# LEDproject_11_18_18.net
KiCad netlist of a schematic drawn in EAGLE
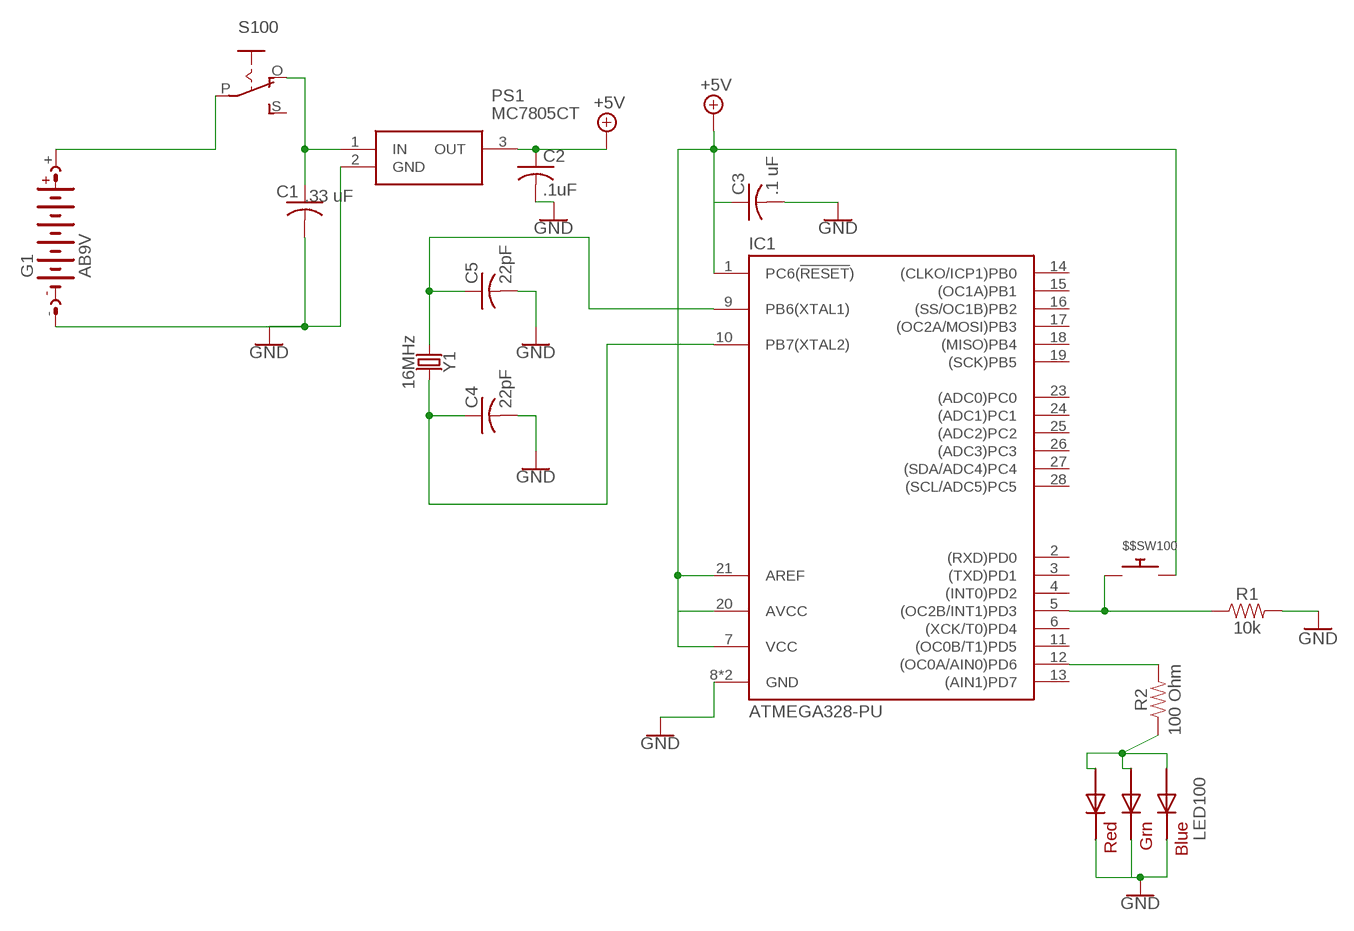
[diagram p0: schematic, sheet 1]

(export (version "E")
  (design (tool "Eeschema 10.0.6"))
  (components
    (comp (ref "$$SW100")
      (value "SWITCH_PUSHBUTTONEVQ-PE")
      (footprint "eagle-import:TACT_PANA-EVQ")
      (libsource (lib "eagle-import") (part "SWITCH_PUSHBUTTONEVQ-PE"))
    )
    (comp (ref "C1")
      (value "C-US025-030X050")
      (footprint "eagle-import:C025-030X050")
      (fields (field (name "BYPASS1") ".33 uF"))
      (libsource (lib "eagle-import") (part "C-US025-030X050"))
    )
    (comp (ref "C2")
      (value ".1uF")
      (footprint "eagle-import:C025-030X050")
      (libsource (lib "eagle-import") (part "C-US025-030X050"))
    )
    (comp (ref "C3")
      (value ".1 uF")
      (footprint "eagle-import:C025-030X050")
      (libsource (lib "eagle-import") (part "C-US025-030X050"))
    )
    (comp (ref "C4")
      (value "22pF")
      (footprint "eagle-import:C025-030X050")
      (libsource (lib "eagle-import") (part "C-US025-030X050"))
    )
    (comp (ref "C5")
      (value "22pF")
      (footprint "eagle-import:C025-030X050")
      (libsource (lib "eagle-import") (part "C-US025-030X050"))
    )
    (comp (ref "G1")
      (value "AB9V")
      (footprint "eagle-import:AB9V")
      (libsource (lib "eagle-import") (part "AB9V"))
    )
    (comp (ref "IC1")
      (value "ATMEGA328-PU")
      (footprint "eagle-import:DIL28")
      (fields (field (name "DIGI-KEY_PART_NUMBER") "ATMEGA328-PU-ND") (field (name "MF") "Microchip"))
      (libsource (lib "eagle-import") (part "ATMEGA328-PU"))
    )
    (comp (ref "LED100")
      (value "RGBLED5050")
      (footprint "eagle-import:RGBLED5050")
      (libsource (lib "eagle-import") (part "RGBLED5050"))
    )
    (comp (ref "PS1")
      (value "MC7805CT")
      (footprint "eagle-import:TO254P482X997X1968-3P")
      (fields (field (name "MOUSER_PART_NUMBER") "863-MC7805CT"))
      (libsource (lib "eagle-import") (part "MC7805CT"))
    )
    (comp (ref "R1")
      (value "10k")
      (footprint "eagle-import:AXIAL-0.3")
      (libsource (lib "eagle-import") (part "10KOHM-HORIZ-1/6W-5%"))
    )
    (comp (ref "R2")
      (value "100 Ohm")
      (footprint "eagle-import:AXIAL-0.3")
      (libsource (lib "eagle-import") (part "10OHM-HORIZ-1/4W-1%"))
    )
    (comp (ref "S100")
      (value "EG1218S")
      (footprint "eagle-import:EG1218")
      (libsource (lib "eagle-import") (part "EG1218S"))
    )
    (comp (ref "Y1")
      (value "16MHz")
      (footprint "eagle-import:HC49US")
      (libsource (lib "eagle-import") (part "CRYSTAL-16MHZPTH-HC49US"))
    )
  )
  (nets
    (net (code "1") (name "+5V") (class "Default")
      (node (ref "$$SW100") (pin "P$2") (pinfunction "P$2_P$2") (pintype "passive"))
      (node (ref "C2") (pin "1") (pinfunction "1_1") (pintype "passive"))
      (node (ref "C3") (pin "1") (pinfunction "1_1") (pintype "passive"))
      (node (ref "IC1") (pin "1") (pinfunction "PC6(~{RESET})_1") (pintype "bidirectional"))
      (node (ref "IC1") (pin "20") (pinfunction "AVCC_20") (pintype "power_in"))
      (node (ref "IC1") (pin "21") (pinfunction "AREF_21") (pintype "passive"))
      (node (ref "IC1") (pin "7") (pinfunction "VCC_7") (pintype "power_in"))
      (node (ref "PS1") (pin "3") (pinfunction "OUT_3") (pintype "output"))
    )
    (net (code "2") (name "GND") (class "Default")
      (node (ref "C1") (pin "2") (pinfunction "2_2") (pintype "passive"))
      (node (ref "C2") (pin "2") (pinfunction "2_2") (pintype "passive"))
      (node (ref "C3") (pin "2") (pinfunction "2_2") (pintype "passive"))
      (node (ref "C4") (pin "2") (pinfunction "2_2") (pintype "passive"))
      (node (ref "C5") (pin "2") (pinfunction "2_2") (pintype "passive"))
      (node (ref "G1") (pin "-") (pinfunction "-_-") (pintype "passive"))
      (node (ref "IC1") (pin "22") (pinfunction "GND_22") (pintype "power_in"))
      (node (ref "IC1") (pin "8") (pinfunction "GND_8") (pintype "power_in"))
      (node (ref "LED100") (pin "4") (pinfunction "BLUE_C_4") (pintype "bidirectional"))
      (node (ref "LED100") (pin "5") (pinfunction "RED_C_5") (pintype "bidirectional"))
      (node (ref "LED100") (pin "6") (pinfunction "GREEN_C_6") (pintype "bidirectional"))
      (node (ref "PS1") (pin "2") (pinfunction "GND_2") (pintype "power_in"))
      (node (ref "R1") (pin "P$2") (pinfunction "2_P$2") (pintype "passive"))
    )
    (net (code "3") (name "Net-(G1-Pad+)") (class "Default")
      (node (ref "G1") (pin "+") (pinfunction "+_+") (pintype "passive"))
      (node (ref "S100") (pin "P") (pinfunction "P_P") (pintype "passive"))
    )
    (net (code "4") (name "Net-(IC1-(OC0A{slash}AIN0)PD6)") (class "Default")
      (node (ref "IC1") (pin "12") (pinfunction "(OC0A/AIN0)PD6_12") (pintype "bidirectional"))
      (node (ref "R2") (pin "P$2") (pinfunction "2_P$2") (pintype "passive"))
    )
    (net (code "5") (name "Net-(IC1-(OC2B{slash}INT1)PD3)") (class "Default")
      (node (ref "$$SW100") (pin "P$1") (pinfunction "P$1_P$1") (pintype "passive"))
      (node (ref "IC1") (pin "5") (pinfunction "(OC2B/INT1)PD3_5") (pintype "bidirectional"))
      (node (ref "R1") (pin "P$1") (pinfunction "1_P$1") (pintype "passive"))
    )
    (net (code "6") (name "Net-(IC1-PB6(XTAL1))") (class "Default")
      (node (ref "C5") (pin "1") (pinfunction "1_1") (pintype "passive"))
      (node (ref "IC1") (pin "9") (pinfunction "PB6(XTAL1)_9") (pintype "bidirectional"))
      (node (ref "Y1") (pin "1") (pinfunction "1_1") (pintype "passive"))
    )
    (net (code "7") (name "Net-(IC1-PB7(XTAL2))") (class "Default")
      (node (ref "C4") (pin "1") (pinfunction "1_1") (pintype "passive"))
      (node (ref "IC1") (pin "10") (pinfunction "PB7(XTAL2)_10") (pintype "bidirectional"))
      (node (ref "Y1") (pin "2") (pinfunction "2_2") (pintype "passive"))
    )
    (net (code "8") (name "Net-(LED100-BLUE_A)") (class "Default")
      (node (ref "LED100") (pin "1") (pinfunction "GREEN_A_1") (pintype "bidirectional"))
      (node (ref "LED100") (pin "2") (pinfunction "RED_A_2") (pintype "bidirectional"))
      (node (ref "LED100") (pin "3") (pinfunction "BLUE_A_3") (pintype "bidirectional"))
      (node (ref "R2") (pin "P$1") (pinfunction "1_P$1") (pintype "passive"))
    )
    (net (code "9") (name "Net-(PS1-IN)") (class "Default")
      (node (ref "C1") (pin "1") (pinfunction "1_1") (pintype "passive"))
      (node (ref "PS1") (pin "1") (pinfunction "IN_1") (pintype "input"))
      (node (ref "S100") (pin "O") (pinfunction "O_O") (pintype "passive"))
    )
    (net (code "10") (name "unconnected-(IC1-(ADC0)PC0-Pad23)") (class "Default")
      (node (ref "IC1") (pin "23") (pinfunction "(ADC0)PC0_23") (pintype "bidirectional"))
    )
    (net (code "11") (name "unconnected-(IC1-(ADC1)PC1-Pad24)") (class "Default")
      (node (ref "IC1") (pin "24") (pinfunction "(ADC1)PC1_24") (pintype "bidirectional"))
    )
    (net (code "12") (name "unconnected-(IC1-(ADC2)PC2-Pad25)") (class "Default")
      (node (ref "IC1") (pin "25") (pinfunction "(ADC2)PC2_25") (pintype "bidirectional"))
    )
    (net (code "13") (name "unconnected-(IC1-(ADC3)PC3-Pad26)") (class "Default")
      (node (ref "IC1") (pin "26") (pinfunction "(ADC3)PC3_26") (pintype "bidirectional"))
    )
    (net (code "14") (name "unconnected-(IC1-(AIN1)PD7-Pad13)") (class "Default")
      (node (ref "IC1") (pin "13") (pinfunction "(AIN1)PD7_13") (pintype "bidirectional"))
    )
    (net (code "15") (name "unconnected-(IC1-(CLKO{slash}ICP1)PB0-Pad14)") (class "Default")
      (node (ref "IC1") (pin "14") (pinfunction "(CLKO/ICP1)PB0_14") (pintype "bidirectional"))
    )
    (net (code "16") (name "unconnected-(IC1-(INT0)PD2-Pad4)") (class "Default")
      (node (ref "IC1") (pin "4") (pinfunction "(INT0)PD2_4") (pintype "bidirectional"))
    )
    (net (code "17") (name "unconnected-(IC1-(MISO)PB4-Pad18)") (class "Default")
      (node (ref "IC1") (pin "18") (pinfunction "(MISO)PB4_18") (pintype "bidirectional"))
    )
    (net (code "18") (name "unconnected-(IC1-(OC0B{slash}T1)PD5-Pad11)") (class "Default")
      (node (ref "IC1") (pin "11") (pinfunction "(OC0B/T1)PD5_11") (pintype "bidirectional"))
    )
    (net (code "19") (name "unconnected-(IC1-(OC1A)PB1-Pad15)") (class "Default")
      (node (ref "IC1") (pin "15") (pinfunction "(OC1A)PB1_15") (pintype "bidirectional"))
    )
    (net (code "20") (name "unconnected-(IC1-(OC2A{slash}MOSI)PB3-Pad17)") (class "Default")
      (node (ref "IC1") (pin "17") (pinfunction "(OC2A/MOSI)PB3_17") (pintype "bidirectional"))
    )
    (net (code "21") (name "unconnected-(IC1-(RXD)PD0-Pad2)") (class "Default")
      (node (ref "IC1") (pin "2") (pinfunction "(RXD)PD0_2") (pintype "bidirectional"))
    )
    (net (code "22") (name "unconnected-(IC1-(SCK)PB5-Pad19)") (class "Default")
      (node (ref "IC1") (pin "19") (pinfunction "(SCK)PB5_19") (pintype "bidirectional"))
    )
    (net (code "23") (name "unconnected-(IC1-(SCL{slash}ADC5)PC5-Pad28)") (class "Default")
      (node (ref "IC1") (pin "28") (pinfunction "(SCL/ADC5)PC5_28") (pintype "bidirectional"))
    )
    (net (code "24") (name "unconnected-(IC1-(SDA{slash}ADC4)PC4-Pad27)") (class "Default")
      (node (ref "IC1") (pin "27") (pinfunction "(SDA/ADC4)PC4_27") (pintype "bidirectional"))
    )
    (net (code "25") (name "unconnected-(IC1-(SS{slash}OC1B)PB2-Pad16)") (class "Default")
      (node (ref "IC1") (pin "16") (pinfunction "(SS/OC1B)PB2_16") (pintype "bidirectional"))
    )
    (net (code "26") (name "unconnected-(IC1-(TXD)PD1-Pad3)") (class "Default")
      (node (ref "IC1") (pin "3") (pinfunction "(TXD)PD1_3") (pintype "bidirectional"))
    )
    (net (code "27") (name "unconnected-(IC1-(XCK{slash}T0)PD4-Pad6)") (class "Default")
      (node (ref "IC1") (pin "6") (pinfunction "(XCK/T0)PD4_6") (pintype "bidirectional"))
    )
    (net (code "28") (name "unconnected-(S100-PadS)") (class "Default")
      (node (ref "S100") (pin "S") (pinfunction "S_S") (pintype "passive"))
    )
  )
)
